# ProDocument_USB_POWER_2023-10-14.net
KiCad netlist of a schematic drawn in EasyEDA Pro
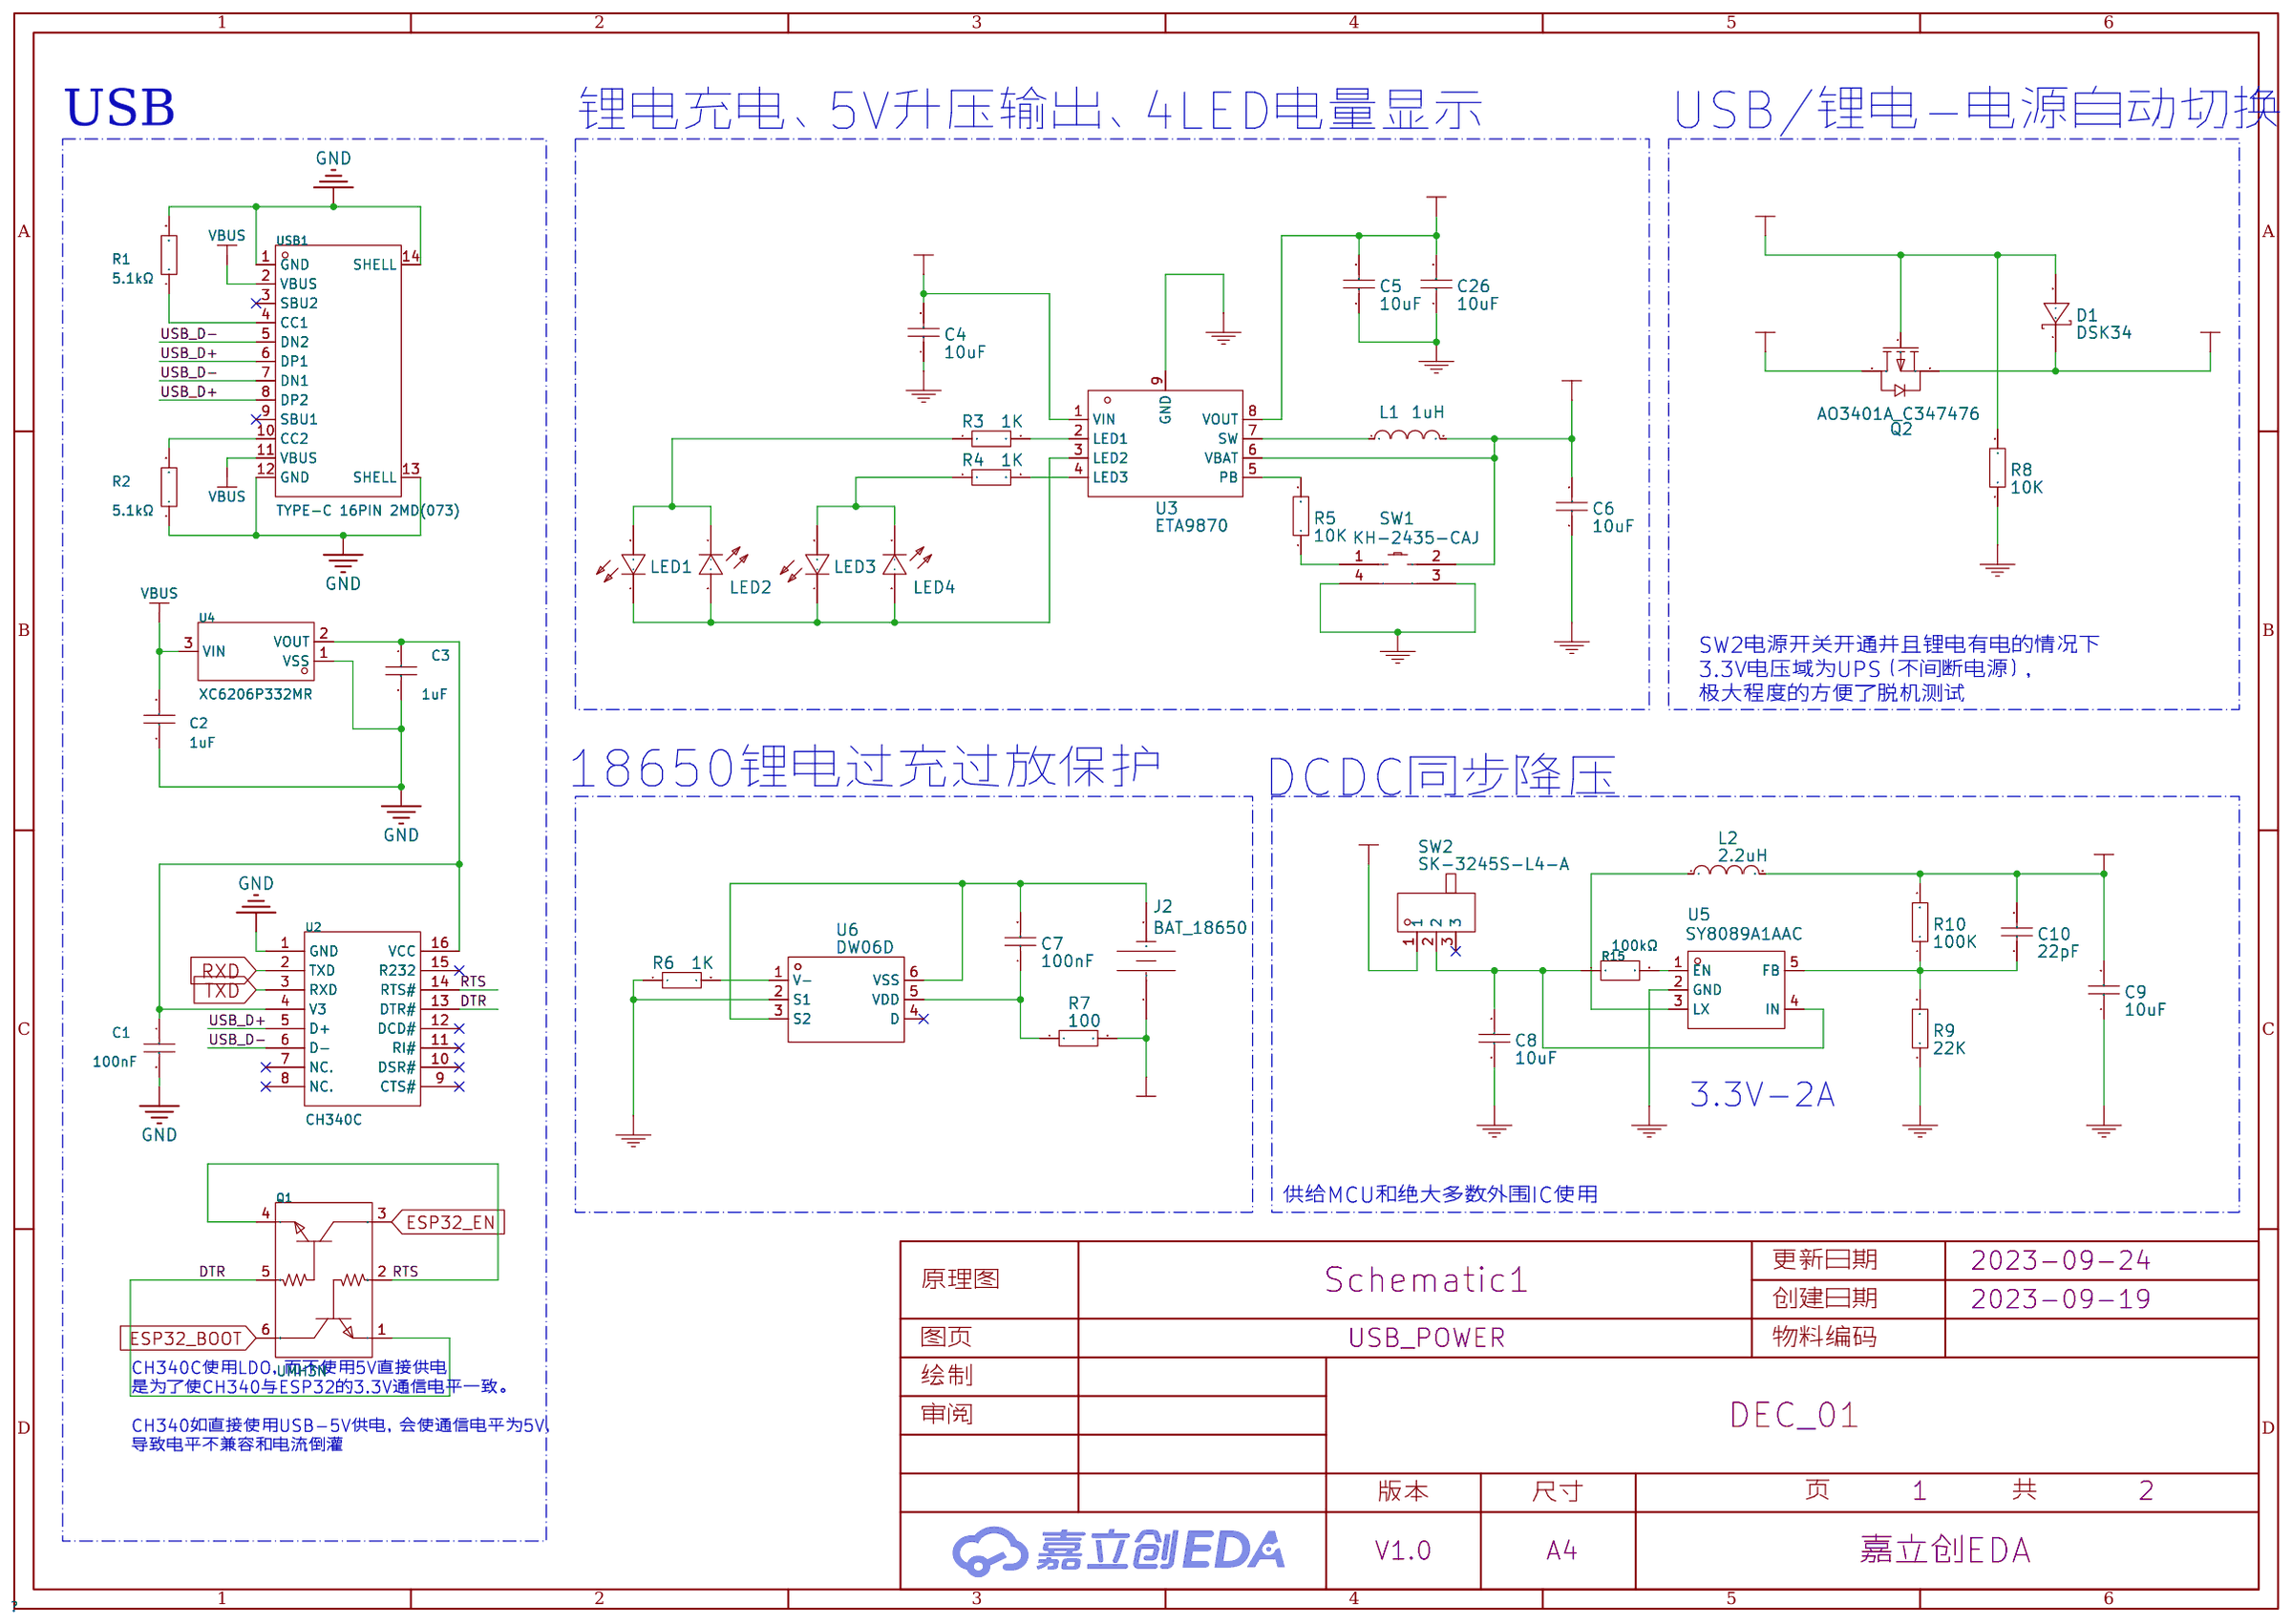
[diagram p0: schematic sheet]

(export (version "E")
  (design (tool "Eeschema 10.0.6"))
  (components
    (comp (ref "C1")
      (value "100nF")
      (footprint "easyedapro:C0603")
      (description "容值:100nF;精度:±10%;额定电压:50V;材质(温度系数):X7R;")
      (fields (field (name "Manufacturer Part") "0603B104K500NT") (field (name "Manufacturer") "FH(风华)"))
      (libsource (lib "easyedapro") (part "0603B104K500NT"))
    )
    (comp (ref "C2")
      (value "1uF")
      (footprint "easyedapro:C0603")
      (description "容值:1uF;精度:±10%;额定电压:50V;材质(温度系数):X5R;")
      (fields
        (field (name "Manufacturer Part") "CL10A105KB8NNNC")
        (field (name "Manufacturer") "SAMSUNG(三星)")
      )
      (libsource (lib "easyedapro") (part "CL10A105KB8NNNC"))
    )
    (comp (ref "C3")
      (value "1uF")
      (footprint "easyedapro:C0603")
      (description "容值:1uF;精度:±10%;额定电压:50V;材质(温度系数):X5R;")
      (fields
        (field (name "Manufacturer Part") "CL10A105KB8NNNC")
        (field (name "Manufacturer") "SAMSUNG(三星)")
      )
      (libsource (lib "easyedapro") (part "CL10A105KB8NNNC"))
    )
    (comp (ref "C4")
      (value "10uF")
      (fields (field (name "Manufacturer Part") "CL05A106MQ5NUNC") (field (name "Manufacturer") "SAMSUNG"))
      (libsource (lib "easyedapro") (part "10uF"))
    )
    (comp (ref "C5")
      (value "10uF")
      (fields (field (name "Manufacturer Part") "CL05A106MQ5NUNC") (field (name "Manufacturer") "SAMSUNG"))
      (libsource (lib "easyedapro") (part "10uF"))
    )
    (comp (ref "C6")
      (value "10uF")
      (fields (field (name "Manufacturer Part") "CL05A106MQ5NUNC") (field (name "Manufacturer") "SAMSUNG"))
      (libsource (lib "easyedapro") (part "10uF"))
    )
    (comp (ref "C7")
      (value "100nF")
      (fields (field (name "Manufacturer Part") "CL05B104KO5NNNC") (field (name "Manufacturer") "SAMSUNG"))
      (libsource (lib "easyedapro") (part "100nF"))
    )
    (comp (ref "C8")
      (value "10uF")
      (fields (field (name "Manufacturer Part") "CL05A106MQ5NUNC") (field (name "Manufacturer") "SAMSUNG"))
      (libsource (lib "easyedapro") (part "10uF"))
    )
    (comp (ref "C9")
      (value "10uF")
      (fields (field (name "Manufacturer Part") "CL05A106MQ5NUNC") (field (name "Manufacturer") "SAMSUNG"))
      (libsource (lib "easyedapro") (part "10uF"))
    )
    (comp (ref "C10")
      (value "22pF")
      (fields (field (name "Manufacturer Part") "0402CG220J500NT") (field (name "Manufacturer") "FH"))
      (libsource (lib "easyedapro") (part "22pF"))
    )
    (comp (ref "C26")
      (value "10uF")
      (fields (field (name "Manufacturer Part") "CL05A106MQ5NUNC") (field (name "Manufacturer") "SAMSUNG"))
      (libsource (lib "easyedapro") (part "10uF"))
    )
    (comp (ref "D1")
      (value "DSK34")
      (fields (field (name "Manufacturer") "MDD"))
      (libsource (lib "easyedapro") (part "DSK34"))
    )
    (comp (ref "J2") (value "BAT_18650") (libsource (lib "easyedapro") (part "BAT_18650")))
    (comp (ref "L1")
      (value "1uH")
      (fields (field (name "Manufacturer Part") "WPN4020H1R0MT") (field (name "Manufacturer") "Sunlord"))
      (libsource (lib "easyedapro") (part "1uH"))
    )
    (comp (ref "L2")
      (value "2.2uH")
      (fields (field (name "Manufacturer Part") "WPN4020H2R2MT") (field (name "Manufacturer") "Sunlord"))
      (libsource (lib "easyedapro") (part "2.2uH"))
    )
    (comp (ref "LED1")
      (value "FC-DA1608BK-470H10")
      (fields (field (name "Manufacturer") "NATIONSTAR"))
      (libsource (lib "easyedapro") (part "FC-DA1608BK-470H10"))
    )
    (comp (ref "LED2")
      (value "FC-DA1608BK-470H10")
      (fields (field (name "Manufacturer") "NATIONSTAR"))
      (libsource (lib "easyedapro") (part "FC-DA1608BK-470H10"))
    )
    (comp (ref "LED3")
      (value "FC-DA1608BK-470H10")
      (fields (field (name "Manufacturer") "NATIONSTAR"))
      (libsource (lib "easyedapro") (part "FC-DA1608BK-470H10"))
    )
    (comp (ref "LED4")
      (value "FC-DA1608BK-470H10")
      (fields (field (name "Manufacturer") "NATIONSTAR"))
      (libsource (lib "easyedapro") (part "FC-DA1608BK-470H10"))
    )
    (comp (ref "Q1")
      (value "UMH3N")
      (footprint "easyedapro:SC-70-6_L2.2-W1.3-P0.65-LS2.1-BR")
      (description "晶体管类型:2个NPN-预偏置;功率(Pd):150mW;集电极电流(Ic):100mA;集射极击穿电压(Vceo):50V;")
      (fields (field (name "Manufacturer") "CJ(江苏长电/长晶)"))
      (libsource (lib "easyedapro") (part "UMH3N"))
    )
    (comp (ref "Q2")
      (value "AO3401A_C347476")
      (fields
        (field (name "Manufacturer Part") "AO3401A")
        (field (name "Manufacturer") "Youtai Semiconductor Co., Ltd.")
      )
      (libsource (lib "easyedapro") (part "AO3401A_C347476"))
    )
    (comp (ref "R1")
      (value "5.1kΩ")
      (footprint "easyedapro:R0603")
      (description "电阻类型:厚膜电阻;阻值:5.1kΩ;精度:±1%;功率:100mW;")
      (fields
        (field (name "Manufacturer Part") "0603WAF5101T5E")
        (field (name "Manufacturer") "UNI-ROYAL(厚声)")
      )
      (libsource (lib "easyedapro") (part "0603WAF5101T5E"))
    )
    (comp (ref "R2")
      (value "5.1kΩ")
      (footprint "easyedapro:R0603")
      (description "电阻类型:厚膜电阻;阻值:5.1kΩ;精度:±1%;功率:100mW;")
      (fields
        (field (name "Manufacturer Part") "0603WAF5101T5E")
        (field (name "Manufacturer") "UNI-ROYAL(厚声)")
      )
      (libsource (lib "easyedapro") (part "0603WAF5101T5E"))
    )
    (comp (ref "R3")
      (value "1K")
      (fields (field (name "Manufacturer Part") "0402WGF1001TCE") (field (name "Manufacturer") "UniOhm"))
      (libsource (lib "easyedapro") (part "1K"))
    )
    (comp (ref "R4")
      (value "1K")
      (fields (field (name "Manufacturer Part") "0402WGF1001TCE") (field (name "Manufacturer") "UniOhm"))
      (libsource (lib "easyedapro") (part "1K"))
    )
    (comp (ref "R5")
      (value "10K")
      (fields (field (name "Manufacturer Part") "0402WGF1002TCE") (field (name "Manufacturer") "UniOhm"))
      (libsource (lib "easyedapro") (part "10K"))
    )
    (comp (ref "R6")
      (value "1K")
      (fields (field (name "Manufacturer Part") "0402WGF1001TCE") (field (name "Manufacturer") "UniOhm"))
      (libsource (lib "easyedapro") (part "1K"))
    )
    (comp (ref "R7")
      (value "100")
      (fields (field (name "Manufacturer Part") "0402WGF1000TCE") (field (name "Manufacturer") "UniOhm"))
      (libsource (lib "easyedapro") (part "100"))
    )
    (comp (ref "R8")
      (value "10K")
      (fields (field (name "Manufacturer Part") "0402WGF1002TCE") (field (name "Manufacturer") "UniOhm"))
      (libsource (lib "easyedapro") (part "10K"))
    )
    (comp (ref "R9")
      (value "22K")
      (fields (field (name "Manufacturer Part") "0402WGF2202TCE") (field (name "Manufacturer") "UniOhm"))
      (libsource (lib "easyedapro") (part "22K"))
    )
    (comp (ref "R10")
      (value "100K")
      (fields (field (name "Manufacturer Part") "0402WGF1003TCE") (field (name "Manufacturer") "UniOhm"))
      (libsource (lib "easyedapro") (part "100K"))
    )
    (comp (ref "R15")
      (value "100kΩ")
      (footprint "easyedapro:RES-SMD_L1.6-W0.8-P1.4")
      (description "阻值:100kΩ;功率:100mW;")
      (fields
        (field (name "Manufacturer Part") "HoLTT0603-1/10W-100KR-1%")
        (field (name "Manufacturer") "Milliohm(毫欧)")
      )
      (libsource (lib "easyedapro") (part "HOLTT0603-1/10W-100KR-1%"))
    )
    (comp (ref "SW1")
      (value "KH-2435-CAJ")
      (fields (field (name "Manufacturer Part") "1TS003B-1600-3500A") (field (name "Manufacturer") "HYP"))
      (libsource (lib "easyedapro") (part "KH-2435-CAJ"))
    )
    (comp (ref "SW2")
      (value "SK-3245S-L4-A")
      (fields (field (name "Manufacturer") "XKB Enterprise"))
      (libsource (lib "easyedapro") (part "SK-3245S-L4-A"))
    )
    (comp (ref "U2")
      (value "CH340C")
      (footprint "easyedapro:SOP-16_L10.0-W3.9-P1.27-LS6.0-BL")
      (description "应用功能:收发器;接口协议:USB 2.0;数据速率:2Mbps;")
      (fields (field (name "Manufacturer") "WCH(南京沁恒)"))
      (libsource (lib "easyedapro") (part "CH340C"))
    )
    (comp (ref "U3")
      (value "ETA9870")
      (fields (field (name "Manufacturer") "钰泰半导体ETA"))
      (libsource (lib "easyedapro") (part "ETA9870"))
    )
    (comp (ref "U4")
      (value "XC6206P332MR")
      (footprint "easyedapro:SOT-23-3_L3.0-W1.7-P0.95-LS2.9-BR")
      (description "输出类型:固定;输出极性:正;最大输入电压:8V;输出电压:3.3V;输出电流:250mA;电源纹波抑制比(PSRR):40dB@(1kHz);")
      (fields (field (name "Manufacturer") "UMW(友台半导体)"))
      (libsource (lib "easyedapro") (part "XC6206P332MR_C347376"))
    )
    (comp (ref "U5")
      (value "SY8089A1AAC")
      (fields (field (name "Manufacturer") "Silergy Corp"))
      (libsource (lib "easyedapro") (part "SY8089A1AAC"))
    )
    (comp (ref "U6")
      (value "DW06D")
      (fields (field (name "Manufacturer") "FM"))
      (libsource (lib "easyedapro") (part "DW06D"))
    )
    (comp (ref "USB1")
      (value "TYPE-C 16PIN 2MD(073)")
      (footprint "easyedapro:USB-C-SMD_TYPE-C-6PIN-2MD-073")
      (description "连接器类型:Type-C;标准:-;公母:母座;触点数量:16;端口数量:1;安装方式:卧贴;额定电流 - 电源:5A;工作温度范围:-25°C~+85°C;")
      (fields (field (name "Manufacturer") "SHOU HAN(首韩)"))
      (libsource (lib "easyedapro") (part "TYPE-C 16PIN 2MD(073)"))
    )
  )
  (nets
    (net (code "1") (name "+3.3V") (class "Default")
      (node (ref "C10") (pin "2") (pinfunction "2_2") (pintype "input"))
      (node (ref "C9") (pin "2") (pinfunction "2_2") (pintype "input"))
      (node (ref "L2") (pin "2") (pinfunction "2_2") (pintype "input"))
      (node (ref "R10") (pin "2") (pinfunction "2_2") (pintype "input"))
    )
    (net (code "2") (name "+5V_OUT") (class "Default")
      (node (ref "C26") (pin "2") (pinfunction "2_2") (pintype "input"))
      (node (ref "C5") (pin "2") (pinfunction "2_2") (pintype "input"))
      (node (ref "U3") (pin "8") (pinfunction "VOUT_8") (pintype "input"))
    )
    (net (code "3") (name "/DTR") (class "Default")
      (node (ref "Q1") (pin "1") (pinfunction "E_1") (pintype "input"))
      (node (ref "Q1") (pin "5") (pinfunction "B_5") (pintype "input"))
      (node (ref "U2") (pin "13") (pinfunction "DTR#_13") (pintype "input"))
    )
    (net (code "4") (name "/RTS") (class "Default")
      (node (ref "Q1") (pin "2") (pinfunction "B_2") (pintype "input"))
      (node (ref "Q1") (pin "4") (pinfunction "E_4") (pintype "input"))
      (node (ref "U2") (pin "14") (pinfunction "RTS#_14") (pintype "input"))
    )
    (net (code "5") (name "/USB_D+") (class "Default")
      (node (ref "U2") (pin "5") (pinfunction "D+_5") (pintype "input"))
      (node (ref "USB1") (pin "6") (pinfunction "DP1_6") (pintype "input"))
      (node (ref "USB1") (pin "8") (pinfunction "DP2_8") (pintype "input"))
    )
    (net (code "6") (name "/USB_D-") (class "Default")
      (node (ref "U2") (pin "6") (pinfunction "D-_6") (pintype "input"))
      (node (ref "USB1") (pin "5") (pinfunction "DN2_5") (pintype "input"))
      (node (ref "USB1") (pin "7") (pinfunction "DN1_7") (pintype "input"))
    )
    (net (code "7") (name "ESP32_BOOT") (class "Default")
      (node (ref "Q1") (pin "6") (pinfunction "C_6") (pintype "input"))
    )
    (net (code "8") (name "ESP32_EN") (class "Default")
      (node (ref "Q1") (pin "3") (pinfunction "C_3") (pintype "input"))
    )
    (net (code "9") (name "GND") (class "Default")
      (node (ref "C1") (pin "2") (pinfunction "2_2") (pintype "input"))
      (node (ref "C2") (pin "1") (pinfunction "1_1") (pintype "input"))
      (node (ref "C26") (pin "1") (pinfunction "1_1") (pintype "input"))
      (node (ref "C3") (pin "1") (pinfunction "1_1") (pintype "input"))
      (node (ref "C4") (pin "1") (pinfunction "1_1") (pintype "input"))
      (node (ref "C5") (pin "1") (pinfunction "1_1") (pintype "input"))
      (node (ref "C6") (pin "1") (pinfunction "1_1") (pintype "input"))
      (node (ref "C8") (pin "1") (pinfunction "1_1") (pintype "input"))
      (node (ref "C9") (pin "1") (pinfunction "1_1") (pintype "input"))
      (node (ref "R1") (pin "2") (pinfunction "2_2") (pintype "input"))
      (node (ref "R2") (pin "1") (pinfunction "1_1") (pintype "input"))
      (node (ref "R6") (pin "1") (pinfunction "1_1") (pintype "input"))
      (node (ref "R8") (pin "1") (pinfunction "1_1") (pintype "input"))
      (node (ref "R9") (pin "1") (pinfunction "1_1") (pintype "input"))
      (node (ref "SW1") (pin "3") (pinfunction "3_3") (pintype "input"))
      (node (ref "SW1") (pin "4") (pinfunction "4_4") (pintype "input"))
      (node (ref "U2") (pin "1") (pinfunction "GND_1") (pintype "input"))
      (node (ref "U3") (pin "9") (pinfunction "GND_9") (pintype "input"))
      (node (ref "U4") (pin "1") (pinfunction "VSS_1") (pintype "input"))
      (node (ref "U5") (pin "2") (pinfunction "GND_2") (pintype "input"))
      (node (ref "U6") (pin "2") (pinfunction "S1_2") (pintype "input"))
      (node (ref "USB1") (pin "1") (pinfunction "GND_1") (pintype "input"))
      (node (ref "USB1") (pin "12") (pinfunction "GND_12") (pintype "input"))
      (node (ref "USB1") (pin "13") (pinfunction "SHELL_13") (pintype "input"))
      (node (ref "USB1") (pin "14") (pinfunction "SHELL_14") (pintype "input"))
    )
    (net (code "10") (name "Net-(LED1-+)") (class "Default")
      (node (ref "LED1") (pin "2") (pinfunction "+_2") (pintype "input"))
      (node (ref "LED2") (pin "1") (pinfunction "-_1") (pintype "input"))
      (node (ref "R3") (pin "1") (pinfunction "1_1") (pintype "input"))
    )
    (net (code "11") (name "Net-(LED1--)") (class "Default")
      (node (ref "LED1") (pin "1") (pinfunction "-_1") (pintype "input"))
      (node (ref "LED2") (pin "2") (pinfunction "+_2") (pintype "input"))
      (node (ref "LED3") (pin "1") (pinfunction "-_1") (pintype "input"))
      (node (ref "LED4") (pin "2") (pinfunction "+_2") (pintype "input"))
      (node (ref "U3") (pin "3") (pinfunction "LED2_3") (pintype "input"))
    )
    (net (code "12") (name "Net-(LED3-+)") (class "Default")
      (node (ref "LED3") (pin "2") (pinfunction "+_2") (pintype "input"))
      (node (ref "LED4") (pin "1") (pinfunction "-_1") (pintype "input"))
      (node (ref "R4") (pin "1") (pinfunction "1_1") (pintype "input"))
    )
    (net (code "13") (name "Net-(R5-Pad1)") (class "Default")
      (node (ref "R5") (pin "1") (pinfunction "1_1") (pintype "input"))
      (node (ref "SW1") (pin "1") (pinfunction "1_1") (pintype "input"))
    )
    (net (code "14") (name "Net-(U2-V3)") (class "Default")
      (node (ref "C1") (pin "1") (pinfunction "1_1") (pintype "input"))
      (node (ref "C3") (pin "2") (pinfunction "2_2") (pintype "input"))
      (node (ref "U2") (pin "16") (pinfunction "VCC_16") (pintype "input"))
      (node (ref "U2") (pin "4") (pinfunction "V3_4") (pintype "input"))
      (node (ref "U4") (pin "2") (pinfunction "VOUT_2") (pintype "input"))
    )
    (net (code "15") (name "Net-(U3-LED1)") (class "Default")
      (node (ref "R3") (pin "2") (pinfunction "2_2") (pintype "input"))
      (node (ref "U3") (pin "2") (pinfunction "LED1_2") (pintype "input"))
    )
    (net (code "16") (name "Net-(U3-LED3)") (class "Default")
      (node (ref "R4") (pin "2") (pinfunction "2_2") (pintype "input"))
      (node (ref "U3") (pin "4") (pinfunction "LED3_4") (pintype "input"))
    )
    (net (code "17") (name "Net-(U3-PB)") (class "Default")
      (node (ref "R5") (pin "2") (pinfunction "2_2") (pintype "input"))
      (node (ref "U3") (pin "5") (pinfunction "PB_5") (pintype "input"))
    )
    (net (code "18") (name "Net-(U3-SW)") (class "Default")
      (node (ref "L1") (pin "1") (pinfunction "1_1") (pintype "input"))
      (node (ref "U3") (pin "7") (pinfunction "SW_7") (pintype "input"))
    )
    (net (code "19") (name "Net-(U5-EN)") (class "Default")
      (node (ref "R15") (pin "2") (pinfunction "2_2") (pintype "input"))
      (node (ref "U5") (pin "1") (pinfunction "EN_1") (pintype "input"))
    )
    (net (code "20") (name "Net-(U5-FB)") (class "Default")
      (node (ref "C10") (pin "1") (pinfunction "1_1") (pintype "input"))
      (node (ref "R10") (pin "1") (pinfunction "1_1") (pintype "input"))
      (node (ref "R9") (pin "2") (pinfunction "2_2") (pintype "input"))
      (node (ref "U5") (pin "5") (pinfunction "FB_5") (pintype "input"))
    )
    (net (code "21") (name "Net-(U5-IN)") (class "Default")
      (node (ref "C8") (pin "2") (pinfunction "2_2") (pintype "input"))
      (node (ref "R15") (pin "1") (pinfunction "1_1") (pintype "input"))
      (node (ref "SW2") (pin "2") (pinfunction "2_2") (pintype "input"))
      (node (ref "U5") (pin "4") (pinfunction "IN_4") (pintype "input"))
    )
    (net (code "22") (name "Net-(U5-LX)") (class "Default")
      (node (ref "L2") (pin "1") (pinfunction "1_1") (pintype "input"))
      (node (ref "U5") (pin "3") (pinfunction "LX_3") (pintype "input"))
    )
    (net (code "23") (name "Net-(U6-S2)") (class "Default")
      (node (ref "C7") (pin "2") (pinfunction "2_2") (pintype "input"))
      (node (ref "J2") (pin "2") (pinfunction "2_2") (pintype "input"))
      (node (ref "U6") (pin "3") (pinfunction "S2_3") (pintype "input"))
      (node (ref "U6") (pin "6") (pinfunction "VSS_6") (pintype "input"))
    )
    (net (code "24") (name "Net-(U6-V-)") (class "Default")
      (node (ref "R6") (pin "2") (pinfunction "2_2") (pintype "input"))
      (node (ref "U6") (pin "1") (pinfunction "V-_1") (pintype "input"))
    )
    (net (code "25") (name "Net-(U6-VDD)") (class "Default")
      (node (ref "C7") (pin "1") (pinfunction "1_1") (pintype "input"))
      (node (ref "R7") (pin "1") (pinfunction "1_1") (pintype "input"))
      (node (ref "U6") (pin "5") (pinfunction "VDD_5") (pintype "input"))
    )
    (net (code "26") (name "Net-(USB1-CC1)") (class "Default")
      (node (ref "R1") (pin "1") (pinfunction "1_1") (pintype "input"))
      (node (ref "USB1") (pin "4") (pinfunction "CC1_4") (pintype "input"))
    )
    (net (code "27") (name "Net-(USB1-CC2)") (class "Default")
      (node (ref "R2") (pin "2") (pinfunction "2_2") (pintype "input"))
      (node (ref "USB1") (pin "10") (pinfunction "CC2_10") (pintype "input"))
    )
    (net (code "28") (name "RXD") (class "Default")
      (node (ref "U2") (pin "2") (pinfunction "TXD_2") (pintype "input"))
    )
    (net (code "29") (name "TXD") (class "Default")
      (node (ref "U2") (pin "3") (pinfunction "RXD_3") (pintype "input"))
    )
    (net (code "30") (name "VBAT_4.2V") (class "Default")
      (node (ref "C6") (pin "2") (pinfunction "2_2") (pintype "input"))
      (node (ref "J2") (pin "1") (pinfunction "1_1") (pintype "input"))
      (node (ref "L1") (pin "2") (pinfunction "2_2") (pintype "input"))
      (node (ref "Q2") (pin "3") (pinfunction "D_3") (pintype "input"))
      (node (ref "R7") (pin "2") (pinfunction "2_2") (pintype "input"))
      (node (ref "SW1") (pin "2") (pinfunction "2_2") (pintype "input"))
      (node (ref "U3") (pin "6") (pinfunction "VBAT_6") (pintype "input"))
    )
    (net (code "31") (name "VBUS") (class "Default")
      (node (ref "C2") (pin "2") (pinfunction "2_2") (pintype "input"))
      (node (ref "C4") (pin "2") (pinfunction "2_2") (pintype "input"))
      (node (ref "D1") (pin "2") (pinfunction "A_2") (pintype "input"))
      (node (ref "Q2") (pin "1") (pinfunction "G_1") (pintype "input"))
      (node (ref "R8") (pin "2") (pinfunction "2_2") (pintype "input"))
      (node (ref "U3") (pin "1") (pinfunction "VIN_1") (pintype "input"))
      (node (ref "U4") (pin "3") (pinfunction "VIN_3") (pintype "input"))
      (node (ref "USB1") (pin "11") (pinfunction "VBUS_11") (pintype "input"))
      (node (ref "USB1") (pin "2") (pinfunction "VBUS_2") (pintype "input"))
    )
    (net (code "32") (name "VIN") (class "Default")
      (node (ref "D1") (pin "1") (pinfunction "K_1") (pintype "input"))
      (node (ref "Q2") (pin "2") (pinfunction "S_2") (pintype "input"))
      (node (ref "SW2") (pin "1") (pinfunction "1_1") (pintype "input"))
    )
    (net (code "33") (name "unconnected-(SW2-Pad3)") (class "Default")
      (node (ref "SW2") (pin "3") (pinfunction "3_3") (pintype "input+no_connect"))
    )
    (net (code "34") (name "unconnected-(U2-CTS#-Pad9)") (class "Default")
      (node (ref "U2") (pin "9") (pinfunction "CTS#_9") (pintype "input+no_connect"))
    )
    (net (code "35") (name "unconnected-(U2-DCD#-Pad12)") (class "Default")
      (node (ref "U2") (pin "12") (pinfunction "DCD#_12") (pintype "input+no_connect"))
    )
    (net (code "36") (name "unconnected-(U2-DSR#-Pad10)") (class "Default")
      (node (ref "U2") (pin "10") (pinfunction "DSR#_10") (pintype "input+no_connect"))
    )
    (net (code "37") (name "unconnected-(U2-NC.-Pad7)") (class "Default")
      (node (ref "U2") (pin "7") (pinfunction "NC._7") (pintype "input+no_connect"))
    )
    (net (code "38") (name "unconnected-(U2-NC.-Pad8)") (class "Default")
      (node (ref "U2") (pin "8") (pinfunction "NC._8") (pintype "input+no_connect"))
    )
    (net (code "39") (name "unconnected-(U2-R232-Pad15)") (class "Default")
      (node (ref "U2") (pin "15") (pinfunction "R232_15") (pintype "input+no_connect"))
    )
    (net (code "40") (name "unconnected-(U2-RI#-Pad11)") (class "Default")
      (node (ref "U2") (pin "11") (pinfunction "RI#_11") (pintype "input+no_connect"))
    )
    (net (code "41") (name "unconnected-(U6-D-Pad4)") (class "Default")
      (node (ref "U6") (pin "4") (pinfunction "D_4") (pintype "input+no_connect"))
    )
    (net (code "42") (name "unconnected-(USB1-SBU1-Pad9)") (class "Default")
      (node (ref "USB1") (pin "9") (pinfunction "SBU1_9") (pintype "input+no_connect"))
    )
    (net (code "43") (name "unconnected-(USB1-SBU2-Pad3)") (class "Default")
      (node (ref "USB1") (pin "3") (pinfunction "SBU2_3") (pintype "input+no_connect"))
    )
  )
)
